# SmartStormDrainWiringDiagram.net
KiCad netlist of a schematic drawn in EAGLE
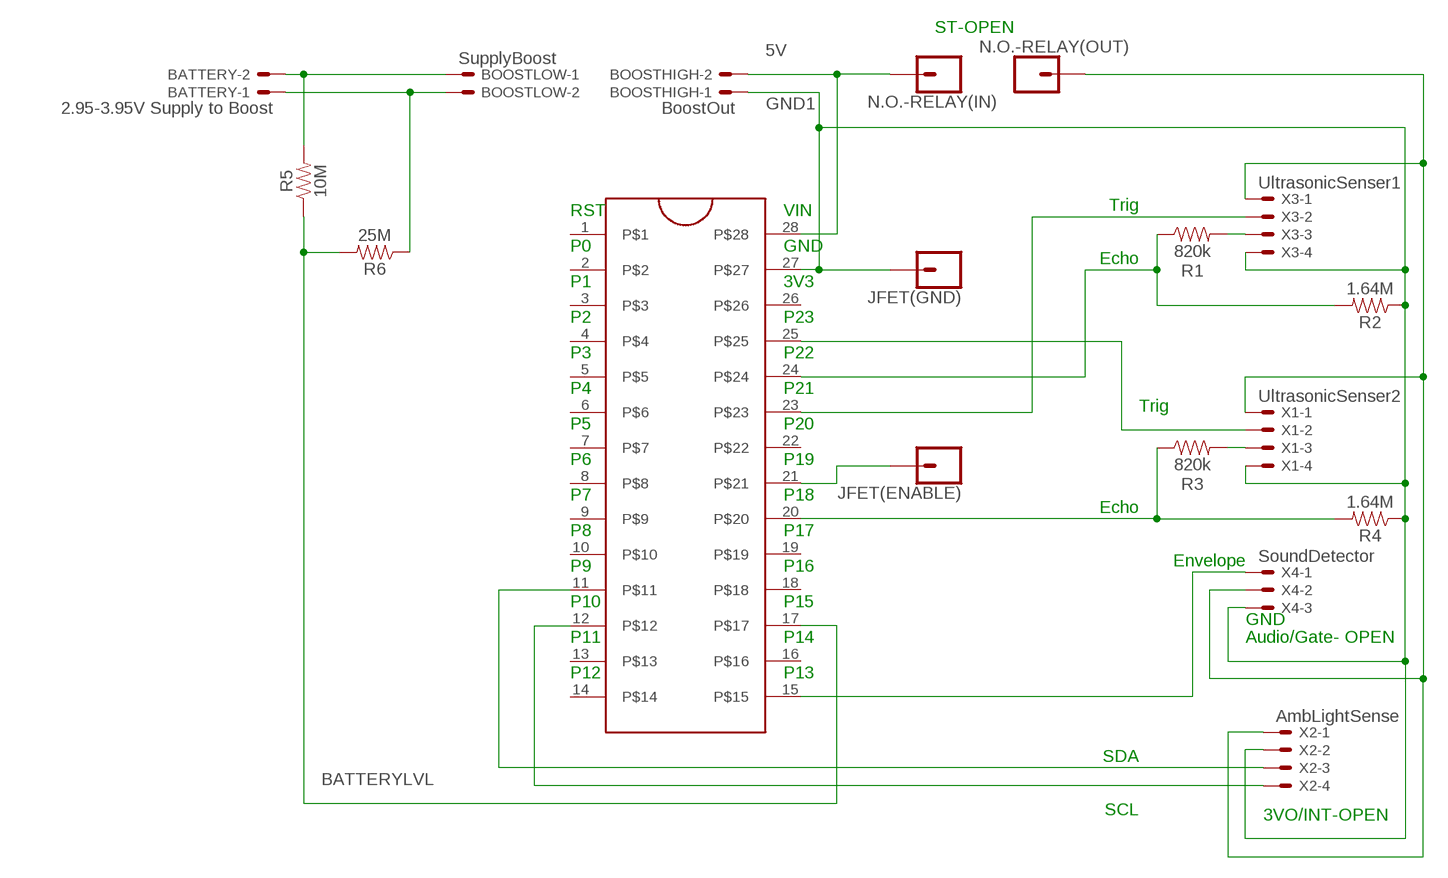
[diagram p0: schematic, sheet 1]

(export (version "E")
  (design (tool "Eeschema 10.0.6"))
  (components
    (comp (ref "BATTERY")
      (value "2.95-3.95V Supply to Boost")
      (footprint "eagle-import:22-23-2021")
      (fields (field (name "MF") "MOLEX") (field (name "MPN") "22-23-2021"))
      (libsource (lib "eagle-import") (part "22-23-2021"))
    )
    (comp (ref "BOOSTHIGH")
      (value "BoostOut")
      (footprint "eagle-import:22-23-2021")
      (fields (field (name "MF") "MOLEX") (field (name "MPN") "22-23-2021"))
      (libsource (lib "eagle-import") (part "22-23-2021"))
    )
    (comp (ref "BOOSTLOW")
      (value "SupplyBoost")
      (footprint "eagle-import:22-23-2021")
      (fields (field (name "MF") "MOLEX") (field (name "MPN") "22-23-2021"))
      (libsource (lib "eagle-import") (part "22-23-2021"))
    )
    (comp (ref "JFET(ENABLE)")
      (value "CONN_01SMTSO-256-ET-0.165DIA")
      (footprint "eagle-import:SMTSO-256-ET-0.165DIA")
      (libsource (lib "eagle-import") (part "CONN_01SMTSO-256-ET-0.165DIA"))
    )
    (comp (ref "JFET(GND)")
      (value "CONN_01SMTSO-256-ET-0.165DIA")
      (footprint "eagle-import:SMTSO-256-ET-0.165DIA")
      (libsource (lib "eagle-import") (part "CONN_01SMTSO-256-ET-0.165DIA"))
    )
    (comp (ref "LOPY4")
      (value "LoPy4")
      (footprint "eagle-import:DIL28-3-ZIF_SOCKET")
      (libsource (lib "eagle-import") (part "ZIFSOCKET-28-3{dblquote}"))
    )
    (comp (ref "N.O.-RELAY(IN)")
      (value "CONN_01SMTSO-256-ET-0.165DIA")
      (footprint "eagle-import:SMTSO-256-ET-0.165DIA")
      (libsource (lib "eagle-import") (part "CONN_01SMTSO-256-ET-0.165DIA"))
    )
    (comp (ref "N.O.-RELAY(OUT)")
      (value "CONN_01SMTSO-256-ET-0.165DIA")
      (footprint "eagle-import:SMTSO-256-ET-0.165DIA")
      (libsource (lib "eagle-import") (part "CONN_01SMTSO-256-ET-0.165DIA"))
    )
    (comp (ref "R1")
      (value "820k")
      (footprint "eagle-import:0603")
      (libsource (lib "eagle-import") (part "1MOHM-0603-1/4W-5%"))
    )
    (comp (ref "R2")
      (value "1.64M")
      (footprint "eagle-import:0603")
      (libsource (lib "eagle-import") (part "1MOHM-0603-1/4W-5%"))
    )
    (comp (ref "R3")
      (value "820k")
      (footprint "eagle-import:0603")
      (libsource (lib "eagle-import") (part "1MOHM-0603-1/4W-5%"))
    )
    (comp (ref "R4")
      (value "1.64M")
      (footprint "eagle-import:0603")
      (libsource (lib "eagle-import") (part "1MOHM-0603-1/4W-5%"))
    )
    (comp (ref "R5")
      (value "10M")
      (footprint "eagle-import:0603")
      (libsource (lib "eagle-import") (part "1MOHM-0603-1/4W-5%"))
    )
    (comp (ref "R6")
      (value "25M")
      (footprint "eagle-import:0603")
      (libsource (lib "eagle-import") (part "1MOHM-0603-1/4W-5%"))
    )
    (comp (ref "X1")
      (value "UltrasonicSenser2")
      (footprint "eagle-import:22-23-2041")
      (fields (field (name "MF") "MOLEX") (field (name "MPN") "22-23-2041"))
      (libsource (lib "eagle-import") (part "22-23-2041"))
    )
    (comp (ref "X2")
      (value "AmbLightSense")
      (footprint "eagle-import:22-23-2041")
      (fields (field (name "MF") "MOLEX") (field (name "MPN") "22-23-2041"))
      (libsource (lib "eagle-import") (part "22-23-2041"))
    )
    (comp (ref "X3")
      (value "UltrasonicSenser1")
      (footprint "eagle-import:22-23-2041")
      (fields (field (name "MF") "MOLEX") (field (name "MPN") "22-23-2041"))
      (libsource (lib "eagle-import") (part "22-23-2041"))
    )
    (comp (ref "X4")
      (value "SoundDetector")
      (footprint "eagle-import:22-23-2031")
      (fields (field (name "MF") "MOLEX") (field (name "MPN") "22-23-2031"))
      (libsource (lib "eagle-import") (part "22-23-2031"))
    )
  )
  (nets
    (net (code "1") (name "/5V") (class "Default")
      (node (ref "BOOSTHIGH") (pin "2") (pinfunction "S_2") (pintype "passive"))
      (node (ref "LOPY4") (pin "28") (pinfunction "P$28_28") (pintype "bidirectional"))
      (node (ref "N.O.-RELAY(IN)") (pin "P$1") (pinfunction "1_P$1") (pintype "passive"))
    )
    (net (code "2") (name "/BATTERYLVL") (class "Default")
      (node (ref "LOPY4") (pin "17") (pinfunction "P$17_17") (pintype "bidirectional"))
      (node (ref "R5") (pin "1") (pinfunction "1_1") (pintype "passive"))
      (node (ref "R6") (pin "2") (pinfunction "2_2") (pintype "passive"))
    )
    (net (code "3") (name "/GND1") (class "Default")
      (node (ref "BOOSTHIGH") (pin "1") (pinfunction "S_1") (pintype "passive"))
      (node (ref "JFET(GND)") (pin "P$1") (pinfunction "1_P$1") (pintype "passive"))
      (node (ref "LOPY4") (pin "27") (pinfunction "P$27_27") (pintype "bidirectional"))
      (node (ref "R2") (pin "1") (pinfunction "1_1") (pintype "passive"))
      (node (ref "R4") (pin "1") (pinfunction "1_1") (pintype "passive"))
      (node (ref "X1") (pin "4") (pinfunction "S_4") (pintype "passive"))
      (node (ref "X2") (pin "2") (pinfunction "S_2") (pintype "passive"))
      (node (ref "X3") (pin "4") (pinfunction "S_4") (pintype "passive"))
      (node (ref "X4") (pin "3") (pinfunction "S_3") (pintype "passive"))
    )
    (net (code "4") (name "Net-(BATTERYA-S)") (class "Default")
      (node (ref "BATTERY") (pin "1") (pinfunction "S_1") (pintype "passive"))
      (node (ref "BOOSTLOW") (pin "2") (pinfunction "S_2") (pintype "passive"))
      (node (ref "R6") (pin "1") (pinfunction "1_1") (pintype "passive"))
    )
    (net (code "5") (name "Net-(BATTERYB-S)") (class "Default")
      (node (ref "BATTERY") (pin "2") (pinfunction "S_2") (pintype "passive"))
      (node (ref "BOOSTLOW") (pin "1") (pinfunction "S_1") (pintype "passive"))
      (node (ref "R5") (pin "2") (pinfunction "2_2") (pintype "passive"))
    )
    (net (code "6") (name "Net-(JFET(ENABLE)-1)") (class "Default")
      (node (ref "JFET(ENABLE)") (pin "P$1") (pinfunction "1_P$1") (pintype "passive"))
      (node (ref "LOPY4") (pin "21") (pinfunction "P$21_21") (pintype "bidirectional"))
    )
    (net (code "7") (name "Net-(LOPY4-P$11)") (class "Default")
      (node (ref "LOPY4") (pin "11") (pinfunction "P$11_11") (pintype "bidirectional"))
      (node (ref "X2") (pin "3") (pinfunction "S_3") (pintype "passive"))
    )
    (net (code "8") (name "Net-(LOPY4-P$12)") (class "Default")
      (node (ref "LOPY4") (pin "12") (pinfunction "P$12_12") (pintype "bidirectional"))
      (node (ref "X2") (pin "4") (pinfunction "S_4") (pintype "passive"))
    )
    (net (code "9") (name "Net-(LOPY4-P$15)") (class "Default")
      (node (ref "LOPY4") (pin "15") (pinfunction "P$15_15") (pintype "bidirectional"))
      (node (ref "X4") (pin "1") (pinfunction "S_1") (pintype "passive"))
    )
    (net (code "10") (name "Net-(LOPY4-P$20)") (class "Default")
      (node (ref "LOPY4") (pin "20") (pinfunction "P$20_20") (pintype "bidirectional"))
      (node (ref "R3") (pin "1") (pinfunction "1_1") (pintype "passive"))
      (node (ref "R4") (pin "2") (pinfunction "2_2") (pintype "passive"))
    )
    (net (code "11") (name "Net-(LOPY4-P$23)") (class "Default")
      (node (ref "LOPY4") (pin "23") (pinfunction "P$23_23") (pintype "bidirectional"))
      (node (ref "X3") (pin "2") (pinfunction "S_2") (pintype "passive"))
    )
    (net (code "12") (name "Net-(LOPY4-P$24)") (class "Default")
      (node (ref "LOPY4") (pin "24") (pinfunction "P$24_24") (pintype "bidirectional"))
      (node (ref "R1") (pin "1") (pinfunction "1_1") (pintype "passive"))
      (node (ref "R2") (pin "2") (pinfunction "2_2") (pintype "passive"))
    )
    (net (code "13") (name "Net-(LOPY4-P$25)") (class "Default")
      (node (ref "LOPY4") (pin "25") (pinfunction "P$25_25") (pintype "bidirectional"))
      (node (ref "X1") (pin "2") (pinfunction "S_2") (pintype "passive"))
    )
    (net (code "14") (name "Net-(N.O.-RELAY(OUT)-1)") (class "Default")
      (node (ref "N.O.-RELAY(OUT)") (pin "P$1") (pinfunction "1_P$1") (pintype "passive"))
      (node (ref "X1") (pin "1") (pinfunction "S_1") (pintype "passive"))
      (node (ref "X2") (pin "1") (pinfunction "S_1") (pintype "passive"))
      (node (ref "X3") (pin "1") (pinfunction "S_1") (pintype "passive"))
      (node (ref "X4") (pin "2") (pinfunction "S_2") (pintype "passive"))
    )
    (net (code "15") (name "Net-(X1C-S)") (class "Default")
      (node (ref "R3") (pin "2") (pinfunction "2_2") (pintype "passive"))
      (node (ref "X1") (pin "3") (pinfunction "S_3") (pintype "passive"))
    )
    (net (code "16") (name "Net-(X3C-S)") (class "Default")
      (node (ref "R1") (pin "2") (pinfunction "2_2") (pintype "passive"))
      (node (ref "X3") (pin "3") (pinfunction "S_3") (pintype "passive"))
    )
    (net (code "17") (name "unconnected-(LOPY4-P$1-Pad1)") (class "Default")
      (node (ref "LOPY4") (pin "1") (pinfunction "P$1_1") (pintype "bidirectional"))
    )
    (net (code "18") (name "unconnected-(LOPY4-P$2-Pad2)") (class "Default")
      (node (ref "LOPY4") (pin "2") (pinfunction "P$2_2") (pintype "bidirectional"))
    )
    (net (code "19") (name "unconnected-(LOPY4-P$3-Pad3)") (class "Default")
      (node (ref "LOPY4") (pin "3") (pinfunction "P$3_3") (pintype "bidirectional"))
    )
    (net (code "20") (name "unconnected-(LOPY4-P$4-Pad4)") (class "Default")
      (node (ref "LOPY4") (pin "4") (pinfunction "P$4_4") (pintype "bidirectional"))
    )
    (net (code "21") (name "unconnected-(LOPY4-P$5-Pad5)") (class "Default")
      (node (ref "LOPY4") (pin "5") (pinfunction "P$5_5") (pintype "bidirectional"))
    )
    (net (code "22") (name "unconnected-(LOPY4-P$6-Pad6)") (class "Default")
      (node (ref "LOPY4") (pin "6") (pinfunction "P$6_6") (pintype "bidirectional"))
    )
    (net (code "23") (name "unconnected-(LOPY4-P$7-Pad7)") (class "Default")
      (node (ref "LOPY4") (pin "7") (pinfunction "P$7_7") (pintype "bidirectional"))
    )
    (net (code "24") (name "unconnected-(LOPY4-P$8-Pad8)") (class "Default")
      (node (ref "LOPY4") (pin "8") (pinfunction "P$8_8") (pintype "bidirectional"))
    )
    (net (code "25") (name "unconnected-(LOPY4-P$9-Pad9)") (class "Default")
      (node (ref "LOPY4") (pin "9") (pinfunction "P$9_9") (pintype "bidirectional"))
    )
    (net (code "26") (name "unconnected-(LOPY4-P$10-Pad10)") (class "Default")
      (node (ref "LOPY4") (pin "10") (pinfunction "P$10_10") (pintype "bidirectional"))
    )
    (net (code "27") (name "unconnected-(LOPY4-P$13-Pad13)") (class "Default")
      (node (ref "LOPY4") (pin "13") (pinfunction "P$13_13") (pintype "bidirectional"))
    )
    (net (code "28") (name "unconnected-(LOPY4-P$14-Pad14)") (class "Default")
      (node (ref "LOPY4") (pin "14") (pinfunction "P$14_14") (pintype "bidirectional"))
    )
    (net (code "29") (name "unconnected-(LOPY4-P$16-Pad16)") (class "Default")
      (node (ref "LOPY4") (pin "16") (pinfunction "P$16_16") (pintype "bidirectional"))
    )
    (net (code "30") (name "unconnected-(LOPY4-P$18-Pad18)") (class "Default")
      (node (ref "LOPY4") (pin "18") (pinfunction "P$18_18") (pintype "bidirectional"))
    )
    (net (code "31") (name "unconnected-(LOPY4-P$19-Pad19)") (class "Default")
      (node (ref "LOPY4") (pin "19") (pinfunction "P$19_19") (pintype "bidirectional"))
    )
    (net (code "32") (name "unconnected-(LOPY4-P$22-Pad22)") (class "Default")
      (node (ref "LOPY4") (pin "22") (pinfunction "P$22_22") (pintype "bidirectional"))
    )
    (net (code "33") (name "unconnected-(LOPY4-P$26-Pad26)") (class "Default")
      (node (ref "LOPY4") (pin "26") (pinfunction "P$26_26") (pintype "bidirectional"))
    )
  )
)
